# USRF02.net
KiCad netlist of a schematic drawn in Altium Designer
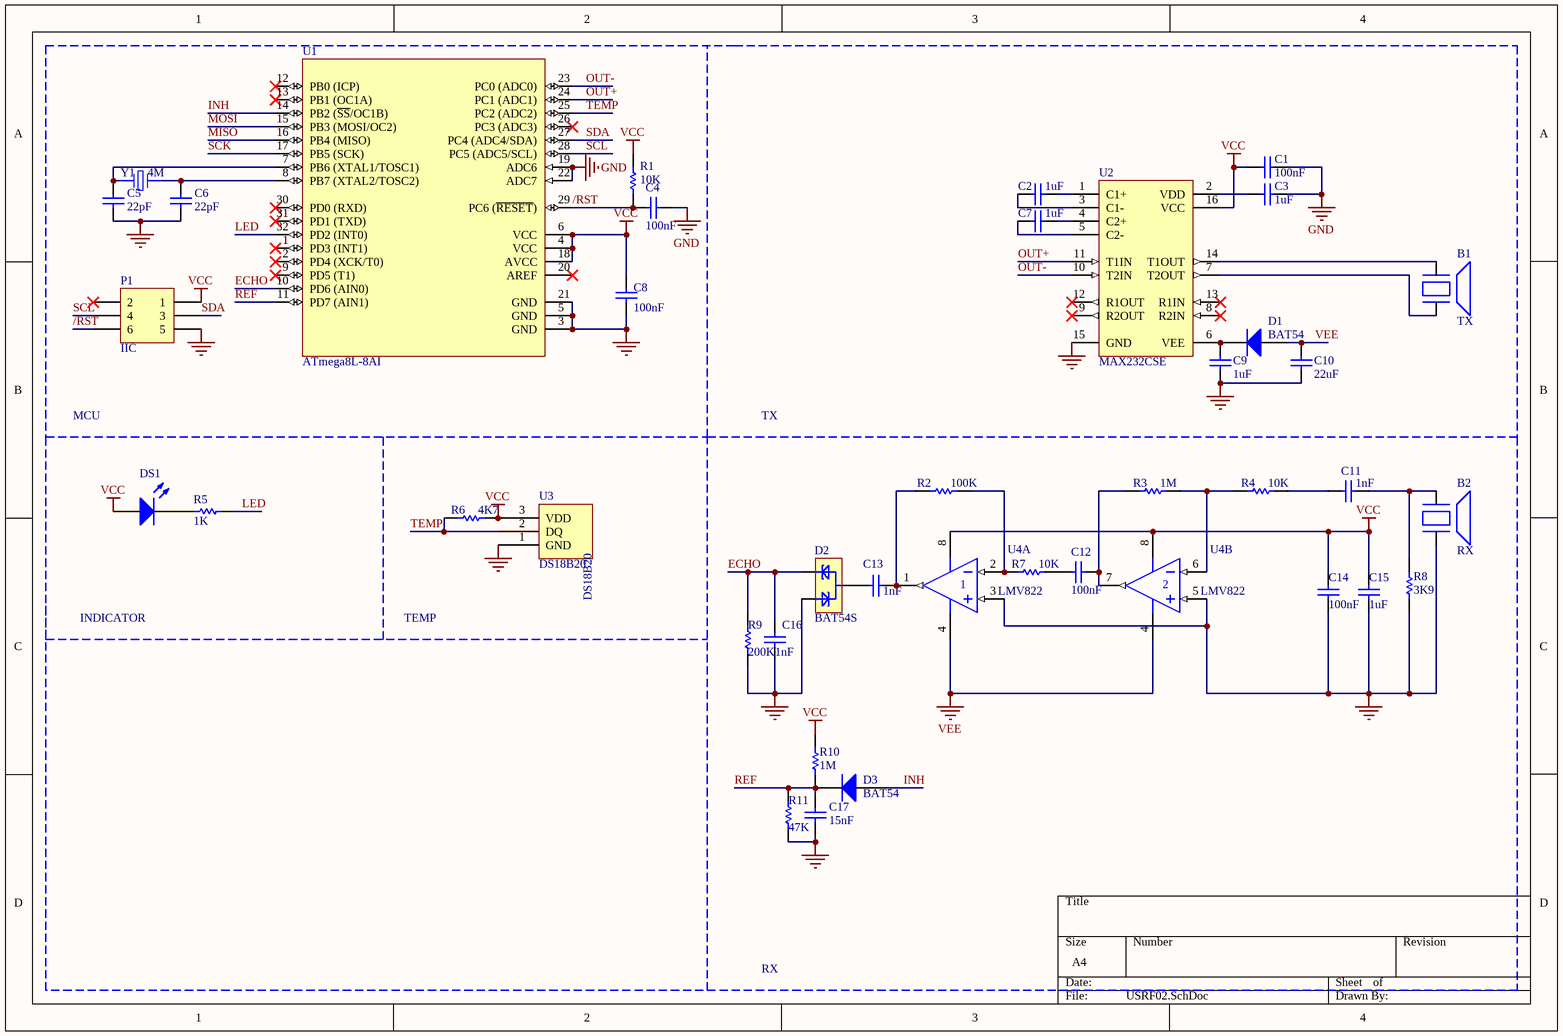
[diagram p0: USRF02.SchDoc]

(export (version "E")
  (design (tool "Eeschema 10.0.6"))
  (components
    (comp (ref "B1")
      (value "TX")
      (footprint "TCx40-12T/R/TR")
      (description "Ultrasonic TX/RX")
      (libsource (lib "Custom Lib") (part "Ultrasonic TX/RX"))
    )
    (comp (ref "B2")
      (value "RX")
      (footprint "TCx40-12T/R/TR")
      (description "Ultrasonic TX/RX")
      (libsource (lib "Custom Lib") (part "Ultrasonic TX/RX"))
    )
    (comp (ref "C1")
      (value "100nF")
      (footprint "CAPC2012N")
      (description "Capacitor")
      (fields (field (name "PUBLISHER") "Altium Limited"))
      (libsource (lib "Miscellaneous Devices") (part "Cap"))
    )
    (comp (ref "C2")
      (value "1uF")
      (footprint "CAPC2012N")
      (description "Capacitor")
      (fields (field (name "PUBLISHER") "Altium Limited"))
      (libsource (lib "Miscellaneous Devices") (part "Cap"))
    )
    (comp (ref "C3")
      (value "1uF")
      (footprint "CAPC2012N")
      (description "Capacitor")
      (fields (field (name "PUBLISHER") "Altium Limited"))
      (libsource (lib "Miscellaneous Devices") (part "Cap"))
    )
    (comp (ref "C4")
      (value "100nF")
      (footprint "CAPC2012N")
      (description "Capacitor")
      (fields (field (name "PUBLISHER") "Altium Limited"))
      (libsource (lib "Miscellaneous Devices") (part "Cap"))
    )
    (comp (ref "C5")
      (value "22pF")
      (footprint "CAPC2012N")
      (description "Capacitor")
      (fields (field (name "PUBLISHER") "Altium Limited"))
      (libsource (lib "Miscellaneous Devices") (part "Cap"))
    )
    (comp (ref "C6")
      (value "22pF")
      (footprint "CAPC2012N")
      (description "Capacitor")
      (fields (field (name "PUBLISHER") "Altium Limited"))
      (libsource (lib "Miscellaneous Devices") (part "Cap"))
    )
    (comp (ref "C7")
      (value "1uF")
      (footprint "CAPC2012N")
      (description "Capacitor")
      (fields (field (name "PUBLISHER") "Altium Limited"))
      (libsource (lib "Miscellaneous Devices") (part "Cap"))
    )
    (comp (ref "C8")
      (value "100nF")
      (footprint "CAPC2012N")
      (description "Capacitor")
      (fields (field (name "PUBLISHER") "Altium Limited"))
      (libsource (lib "Miscellaneous Devices") (part "Cap"))
    )
    (comp (ref "C9")
      (value "1uF")
      (footprint "CAPC2012N")
      (description "Capacitor")
      (fields (field (name "PUBLISHER") "Altium Limited"))
      (libsource (lib "Miscellaneous Devices") (part "Cap"))
    )
    (comp (ref "C10")
      (value "22uF")
      (footprint "CAPC2012N")
      (description "Capacitor")
      (fields (field (name "PUBLISHER") "Altium Limited"))
      (libsource (lib "Miscellaneous Devices") (part "Cap"))
    )
    (comp (ref "C11")
      (value "1nF")
      (footprint "CAPC2012N")
      (description "Capacitor")
      (fields (field (name "PUBLISHER") "Altium Limited"))
      (libsource (lib "Miscellaneous Devices") (part "Cap"))
    )
    (comp (ref "C12")
      (value "100nF")
      (footprint "CAPC2012N")
      (description "Capacitor")
      (fields (field (name "PUBLISHER") "Altium Limited"))
      (libsource (lib "Miscellaneous Devices") (part "Cap"))
    )
    (comp (ref "C13")
      (value "1nF")
      (footprint "CAPC2012N")
      (description "Capacitor")
      (fields (field (name "PUBLISHER") "Altium Limited"))
      (libsource (lib "Miscellaneous Devices") (part "Cap"))
    )
    (comp (ref "C14")
      (value "100nF")
      (footprint "CAPC2012N")
      (description "Capacitor")
      (fields (field (name "PUBLISHER") "Altium Limited"))
      (libsource (lib "Miscellaneous Devices") (part "Cap"))
    )
    (comp (ref "C15")
      (value "1uF")
      (footprint "CAPC2012N")
      (description "Capacitor")
      (fields (field (name "PUBLISHER") "Altium Limited"))
      (libsource (lib "Miscellaneous Devices") (part "Cap"))
    )
    (comp (ref "C16")
      (value "1nF")
      (footprint "CAPC2012N")
      (description "Capacitor")
      (fields (field (name "PUBLISHER") "Altium Limited"))
      (libsource (lib "Miscellaneous Devices") (part "Cap"))
    )
    (comp (ref "C17")
      (value "15nF")
      (footprint "CAPC2012N")
      (description "Capacitor")
      (fields (field (name "PUBLISHER") "Altium Limited"))
      (libsource (lib "Miscellaneous Devices") (part "Cap"))
    )
    (comp (ref "D1")
      (value "BAT54")
      (footprint "CD2012-0805")
      (description "High Conductance Fast Diode")
      (fields (field (name "PUBLISHER") "Altium Limited"))
      (libsource (lib "Miscellaneous Devices") (part "Diode 1N4148"))
    )
    (comp (ref "D2")
      (value "BAT54S")
      (footprint "SOT-23_L")
      (description "Schottky Diodes")
      (libsource (lib "Custom Lib") (part "BAT54S"))
    )
    (comp (ref "D3")
      (value "BAT54")
      (footprint "CD2012-0805")
      (description "High Conductance Fast Diode")
      (fields (field (name "PUBLISHER") "Altium Limited"))
      (libsource (lib "Miscellaneous Devices") (part "Diode 1N4148"))
    )
    (comp (ref "DS1")
      (value "LED3")
      (footprint "CD2012-0805")
      (description "Typical BLUE SiC LED")
      (fields (field (name "PUBLISHER") "Altium Limited"))
      (libsource (lib "Miscellaneous Devices") (part "LED3"))
    )
    (comp (ref "P1")
      (value "IIC")
      (footprint "HDR2X3")
      (description "Header, 3-Pin, Dual row")
      (fields (field (name "PUBLISHER") "Altium Limited"))
      (libsource (lib "Miscellaneous Connectors") (part "Header 3X2"))
    )
    (comp (ref "R1")
      (value "10K")
      (footprint "RESC2012N")
      (description "Resistor")
      (fields (field (name "PUBLISHER") "Altium Limited"))
      (libsource (lib "Miscellaneous Devices") (part "Res1"))
    )
    (comp (ref "R2")
      (value "100K")
      (footprint "RESC2012N")
      (description "Resistor")
      (fields (field (name "PUBLISHER") "Altium Limited"))
      (libsource (lib "Miscellaneous Devices") (part "Res1"))
    )
    (comp (ref "R3")
      (value "1M")
      (footprint "RESC2012N")
      (description "Resistor")
      (fields (field (name "PUBLISHER") "Altium Limited"))
      (libsource (lib "Miscellaneous Devices") (part "Res1"))
    )
    (comp (ref "R4")
      (value "10K")
      (footprint "RESC2012N")
      (description "Resistor")
      (fields (field (name "PUBLISHER") "Altium Limited"))
      (libsource (lib "Miscellaneous Devices") (part "Res1"))
    )
    (comp (ref "R5")
      (value "1K")
      (footprint "RESC2012N")
      (description "Resistor")
      (fields (field (name "PUBLISHER") "Altium Limited"))
      (libsource (lib "Miscellaneous Devices") (part "Res1"))
    )
    (comp (ref "R6")
      (value "4K7")
      (footprint "RESC2012N")
      (description "Resistor")
      (fields (field (name "PUBLISHER") "Altium Limited"))
      (libsource (lib "Miscellaneous Devices") (part "Res1"))
    )
    (comp (ref "R7")
      (value "10K")
      (footprint "RESC2012N")
      (description "Resistor")
      (fields (field (name "PUBLISHER") "Altium Limited"))
      (libsource (lib "Miscellaneous Devices") (part "Res1"))
    )
    (comp (ref "R8")
      (value "3K9")
      (footprint "RESC2012N")
      (description "Resistor")
      (fields (field (name "PUBLISHER") "Altium Limited"))
      (libsource (lib "Miscellaneous Devices") (part "Res1"))
    )
    (comp (ref "R9")
      (value "200K")
      (footprint "RESC2012N")
      (description "Resistor")
      (fields (field (name "PUBLISHER") "Altium Limited"))
      (libsource (lib "Miscellaneous Devices") (part "Res1"))
    )
    (comp (ref "R10")
      (value "1M")
      (footprint "RESC2012N")
      (description "Resistor")
      (fields (field (name "PUBLISHER") "Altium Limited"))
      (libsource (lib "Miscellaneous Devices") (part "Res1"))
    )
    (comp (ref "R11")
      (value "47K")
      (footprint "RESC2012N")
      (description "Resistor")
      (fields (field (name "PUBLISHER") "Altium Limited"))
      (libsource (lib "Miscellaneous Devices") (part "Res1"))
    )
    (comp (ref "U1")
      (value "ATmega8L-8AI")
      (footprint "32A_N")
      (description "8-Bit AVR Microcontroller with 8K Bytes of In-System Programmable Flash Memory")
      (fields (field (name "PUBLISHER") "Altium Limited"))
      (libsource (lib "Atmel Microcontroller 8-Bit AVR") (part "ATmega8L-8AI"))
    )
    (comp (ref "U2")
      (value "MAX232CSE")
      (footprint "NSO16_N")
      (description "+5V Powered, Multi-Channel RS-232 Driver/Receiver")
      (fields (field (name "PUBLISHER") "Altium Limited"))
      (libsource (lib "Maxim Communication Transceiver") (part "MAX232CSE"))
    )
    (comp (ref "U3")
      (value "DS18B20")
      (footprint "TO-92 (In Line)")
      (description "Programmable Resolution 1-Wire Digital Thermometer")
      (libsource (lib "Custom Lib") (part "DS18B20"))
    )
    (comp (ref "U4")
      (value "LMV822")
      (footprint "M08A_N")
      (description "Dual General-Purpose, Low-Voltage Rail-to-Rail Output Operational Amplifier")
      (fields (field (name "PUBLISHER") "Altium Limited"))
      (libsource (lib "NSC Operational Amplifier") (part "LMV358M"))
    )
    (comp (ref "Y1")
      (value "4M")
      (footprint "Crystal Oscillator 1")
      (description "2 Pins crystal")
      (libsource (lib "Custom Lib") (part "Crystal Oscillator 1"))
    )
  )
  (nets
    (net (code "1") (name "/ECHO") (class "Default")
      (node (ref "C16") (pin "1") (pinfunction "1_1") (pintype "passive"))
      (node (ref "D2") (pin "2") (pinfunction "2_2") (pintype "passive"))
      (node (ref "R9") (pin "2") (pinfunction "2_2") (pintype "passive"))
      (node (ref "U1") (pin "10") (pinfunction "PD6_(AIN0)_10") (pintype "bidirectional"))
    )
    (net (code "2") (name "/INH") (class "Default")
      (node (ref "D3") (pin "1") (pinfunction "A_1") (pintype "passive"))
      (node (ref "U1") (pin "14") (pinfunction "PB2_(~{SS}/OC1B)_14") (pintype "bidirectional"))
    )
    (net (code "3") (name "/LED") (class "Default")
      (node (ref "R5") (pin "2") (pinfunction "2_2") (pintype "passive"))
      (node (ref "U1") (pin "32") (pinfunction "PD2_(INT0)_32") (pintype "bidirectional"))
    )
    (net (code "4") (name "/MISO") (class "Default")
      (node (ref "U1") (pin "16") (pinfunction "PB4_(MISO)_16") (pintype "bidirectional"))
    )
    (net (code "5") (name "/MOSI") (class "Default")
      (node (ref "U1") (pin "15") (pinfunction "PB3_(MOSI/OC2)_15") (pintype "bidirectional"))
    )
    (net (code "6") (name "/OUT+") (class "Default")
      (node (ref "U1") (pin "24") (pinfunction "PC1_(ADC1)_24") (pintype "bidirectional"))
      (node (ref "U2") (pin "11") (pinfunction "T1IN_11") (pintype "input"))
    )
    (net (code "7") (name "/OUT-") (class "Default")
      (node (ref "U1") (pin "23") (pinfunction "PC0_(ADC0)_23") (pintype "bidirectional"))
      (node (ref "U2") (pin "10") (pinfunction "T2IN_10") (pintype "input"))
    )
    (net (code "8") (name "/REF") (class "Default")
      (node (ref "C17") (pin "1") (pinfunction "1_1") (pintype "passive"))
      (node (ref "D3") (pin "2") (pinfunction "K_2") (pintype "passive"))
      (node (ref "R10") (pin "2") (pinfunction "2_2") (pintype "passive"))
      (node (ref "R11") (pin "1") (pinfunction "1_1") (pintype "passive"))
      (node (ref "U1") (pin "11") (pinfunction "PD7_(AIN1)_11") (pintype "bidirectional"))
    )
    (net (code "9") (name "/SCK") (class "Default")
      (node (ref "U1") (pin "17") (pinfunction "PB5_(SCK)_17") (pintype "bidirectional"))
    )
    (net (code "10") (name "/SCL") (class "Default")
      (node (ref "P1") (pin "4") (pinfunction "4_4") (pintype "passive"))
      (node (ref "U1") (pin "28") (pinfunction "PC5_(ADC5/SCL)_28") (pintype "bidirectional"))
    )
    (net (code "11") (name "/SDA") (class "Default")
      (node (ref "P1") (pin "3") (pinfunction "3_3") (pintype "passive"))
      (node (ref "U1") (pin "27") (pinfunction "PC4_(ADC4/SDA)_27") (pintype "bidirectional"))
    )
    (net (code "12") (name "/TEMP") (class "Default")
      (node (ref "R6") (pin "1") (pinfunction "1_1") (pintype "passive"))
      (node (ref "U1") (pin "25") (pinfunction "PC2_(ADC2)_25") (pintype "bidirectional"))
      (node (ref "U3") (pin "2") (pinfunction "DQ_2") (pintype "passive"))
    )
    (net (code "13") (name "/{slash}RST") (class "Default")
      (node (ref "C4") (pin "1") (pinfunction "1_1") (pintype "passive"))
      (node (ref "P1") (pin "6") (pinfunction "6_6") (pintype "passive"))
      (node (ref "R1") (pin "1") (pinfunction "1_1") (pintype "passive"))
      (node (ref "U1") (pin "29") (pinfunction "PC6_(~{RESET})_29") (pintype "bidirectional"))
    )
    (net (code "14") (name "GND") (class "Default")
      (node (ref "B2") (pin "2") (pinfunction "2_2") (pintype "passive"))
      (node (ref "C1") (pin "2") (pinfunction "2_2") (pintype "passive"))
      (node (ref "C10") (pin "1") (pinfunction "1_1") (pintype "passive"))
      (node (ref "C14") (pin "2") (pinfunction "2_2") (pintype "passive"))
      (node (ref "C15") (pin "2") (pinfunction "2_2") (pintype "passive"))
      (node (ref "C16") (pin "2") (pinfunction "2_2") (pintype "passive"))
      (node (ref "C17") (pin "2") (pinfunction "2_2") (pintype "passive"))
      (node (ref "C3") (pin "2") (pinfunction "2_2") (pintype "passive"))
      (node (ref "C4") (pin "2") (pinfunction "2_2") (pintype "passive"))
      (node (ref "C5") (pin "1") (pinfunction "1_1") (pintype "passive"))
      (node (ref "C6") (pin "1") (pinfunction "1_1") (pintype "passive"))
      (node (ref "C8") (pin "2") (pinfunction "2_2") (pintype "passive"))
      (node (ref "C9") (pin "1") (pinfunction "1_1") (pintype "passive"))
      (node (ref "D2") (pin "1") (pinfunction "1_1") (pintype "passive"))
      (node (ref "P1") (pin "5") (pinfunction "5_5") (pintype "passive"))
      (node (ref "R11") (pin "2") (pinfunction "2_2") (pintype "passive"))
      (node (ref "R8") (pin "1") (pinfunction "1_1") (pintype "passive"))
      (node (ref "R9") (pin "1") (pinfunction "1_1") (pintype "passive"))
      (node (ref "U1") (pin "19") (pinfunction "ADC6_19") (pintype "input"))
      (node (ref "U1") (pin "21") (pinfunction "GND_21") (pintype "power_in"))
      (node (ref "U1") (pin "22") (pinfunction "ADC7_22") (pintype "input"))
      (node (ref "U1") (pin "3") (pinfunction "GND_3") (pintype "power_in"))
      (node (ref "U1") (pin "5") (pinfunction "GND_5") (pintype "power_in"))
      (node (ref "U2") (pin "15") (pinfunction "GND_15") (pintype "power_in"))
      (node (ref "U3") (pin "1") (pinfunction "GND_1") (pintype "passive"))
      (node (ref "U4") (pin "3") (pinfunction "IN+_3") (pintype "input"))
      (node (ref "U4") (pin "5") (pinfunction "IN+_5") (pintype "input"))
    )
    (net (code "15") (name "Net-(B2-Pad1)") (class "Default")
      (node (ref "B2") (pin "1") (pinfunction "1_1") (pintype "passive"))
      (node (ref "C11") (pin "2") (pinfunction "2_2") (pintype "passive"))
      (node (ref "R8") (pin "2") (pinfunction "2_2") (pintype "passive"))
    )
    (net (code "16") (name "Net-(C11-Pad1)") (class "Default")
      (node (ref "C11") (pin "1") (pinfunction "1_1") (pintype "passive"))
      (node (ref "R4") (pin "2") (pinfunction "2_2") (pintype "passive"))
    )
    (net (code "17") (name "Net-(C12-Pad2)") (class "Default")
      (node (ref "C12") (pin "2") (pinfunction "2_2") (pintype "passive"))
      (node (ref "R7") (pin "2") (pinfunction "2_2") (pintype "passive"))
    )
    (net (code "18") (name "Net-(C13-Pad2)") (class "Default")
      (node (ref "C13") (pin "2") (pinfunction "2_2") (pintype "passive"))
      (node (ref "D2") (pin "3") (pinfunction "3_3") (pintype "passive"))
    )
    (net (code "19") (name "Net-(D1-K)") (class "Default")
      (node (ref "C9") (pin "2") (pinfunction "2_2") (pintype "passive"))
      (node (ref "D1") (pin "2") (pinfunction "K_2") (pintype "passive"))
      (node (ref "U2") (pin "6") (pinfunction "VEE_6") (pintype "power_in"))
    )
    (net (code "20") (name "Net-(DS1-K)") (class "Default")
      (node (ref "DS1") (pin "2") (pinfunction "K_2") (pintype "passive"))
      (node (ref "R5") (pin "1") (pinfunction "1_1") (pintype "passive"))
    )
    (net (code "21") (name "Net-(U1-PB6_(XTAL1{slash}TOSC1))") (class "Default")
      (node (ref "C5") (pin "2") (pinfunction "2_2") (pintype "passive"))
      (node (ref "U1") (pin "7") (pinfunction "PB6_(XTAL1/TOSC1)_7") (pintype "bidirectional"))
      (node (ref "Y1") (pin "1") (pinfunction "1_1") (pintype "passive"))
    )
    (net (code "22") (name "Net-(U1-PB7_(XTAL2{slash}TOSC2))") (class "Default")
      (node (ref "C6") (pin "2") (pinfunction "2_2") (pintype "passive"))
      (node (ref "U1") (pin "8") (pinfunction "PB7_(XTAL2/TOSC2)_8") (pintype "bidirectional"))
      (node (ref "Y1") (pin "2") (pinfunction "2_2") (pintype "passive"))
    )
    (net (code "23") (name "Net-(U2-C1+)") (class "Default")
      (node (ref "C2") (pin "1") (pinfunction "1_1") (pintype "passive"))
      (node (ref "U2") (pin "1") (pinfunction "C1+_1") (pintype "passive"))
    )
    (net (code "24") (name "Net-(U2-C1-)") (class "Default")
      (node (ref "C2") (pin "2") (pinfunction "2_2") (pintype "passive"))
      (node (ref "U2") (pin "3") (pinfunction "C1-_3") (pintype "passive"))
    )
    (net (code "25") (name "Net-(U2-C2+)") (class "Default")
      (node (ref "C7") (pin "1") (pinfunction "1_1") (pintype "passive"))
      (node (ref "U2") (pin "4") (pinfunction "C2+_4") (pintype "passive"))
    )
    (net (code "26") (name "Net-(U2-C2-)") (class "Default")
      (node (ref "C7") (pin "2") (pinfunction "2_2") (pintype "passive"))
      (node (ref "U2") (pin "5") (pinfunction "C2-_5") (pintype "passive"))
    )
    (net (code "27") (name "Net-(U2-T1OUT)") (class "Default")
      (node (ref "B1") (pin "1") (pinfunction "1_1") (pintype "passive"))
      (node (ref "U2") (pin "14") (pinfunction "T1OUT_14") (pintype "output"))
    )
    (net (code "28") (name "Net-(U2-T2OUT)") (class "Default")
      (node (ref "B1") (pin "2") (pinfunction "2_2") (pintype "passive"))
      (node (ref "U2") (pin "7") (pinfunction "T2OUT_7") (pintype "output"))
    )
    (net (code "29") (name "Net-(U2-VDD)") (class "Default")
      (node (ref "C3") (pin "1") (pinfunction "1_1") (pintype "passive"))
      (node (ref "U2") (pin "2") (pinfunction "VDD_2") (pintype "power_in"))
    )
    (net (code "30") (name "Net-(U4A-IN-)") (class "Default")
      (node (ref "R2") (pin "2") (pinfunction "2_2") (pintype "passive"))
      (node (ref "R7") (pin "1") (pinfunction "1_1") (pintype "passive"))
      (node (ref "U4") (pin "2") (pinfunction "IN-_2") (pintype "input"))
    )
    (net (code "31") (name "Net-(U4A-OUT)") (class "Default")
      (node (ref "C13") (pin "1") (pinfunction "1_1") (pintype "passive"))
      (node (ref "R2") (pin "1") (pinfunction "1_1") (pintype "passive"))
      (node (ref "U4") (pin "1") (pinfunction "OUT_1") (pintype "output"))
    )
    (net (code "32") (name "Net-(U4B-IN-)") (class "Default")
      (node (ref "R3") (pin "2") (pinfunction "2_2") (pintype "passive"))
      (node (ref "R4") (pin "1") (pinfunction "1_1") (pintype "passive"))
      (node (ref "U4") (pin "6") (pinfunction "IN-_6") (pintype "input"))
    )
    (net (code "33") (name "Net-(U4B-OUT)") (class "Default")
      (node (ref "C12") (pin "1") (pinfunction "1_1") (pintype "passive"))
      (node (ref "R3") (pin "1") (pinfunction "1_1") (pintype "passive"))
      (node (ref "U4") (pin "7") (pinfunction "OUT_7") (pintype "output"))
    )
    (net (code "34") (name "VCC") (class "Default")
      (node (ref "C1") (pin "1") (pinfunction "1_1") (pintype "passive"))
      (node (ref "C14") (pin "1") (pinfunction "1_1") (pintype "passive"))
      (node (ref "C15") (pin "1") (pinfunction "1_1") (pintype "passive"))
      (node (ref "C8") (pin "1") (pinfunction "1_1") (pintype "passive"))
      (node (ref "DS1") (pin "1") (pinfunction "A_1") (pintype "passive"))
      (node (ref "P1") (pin "1") (pinfunction "1_1") (pintype "passive"))
      (node (ref "R1") (pin "2") (pinfunction "2_2") (pintype "passive"))
      (node (ref "R10") (pin "1") (pinfunction "1_1") (pintype "passive"))
      (node (ref "R6") (pin "2") (pinfunction "2_2") (pintype "passive"))
      (node (ref "U1") (pin "18") (pinfunction "AVCC_18") (pintype "power_in"))
      (node (ref "U1") (pin "4") (pinfunction "VCC_4") (pintype "power_in"))
      (node (ref "U1") (pin "6") (pinfunction "VCC_6") (pintype "power_in"))
      (node (ref "U2") (pin "16") (pinfunction "VCC_16") (pintype "power_in"))
      (node (ref "U3") (pin "3") (pinfunction "VDD_3") (pintype "passive"))
      (node (ref "U4") (pin "8") (pinfunction "V+_8") (pintype "power_in"))
    )
    (net (code "35") (name "VEE") (class "Default")
      (node (ref "C10") (pin "2") (pinfunction "2_2") (pintype "passive"))
      (node (ref "D1") (pin "1") (pinfunction "A_1") (pintype "passive"))
      (node (ref "U4") (pin "4") (pinfunction "V-_4") (pintype "power_in"))
    )
    (net (code "36") (name "unconnected-(P1-Pad2)") (class "Default")
      (node (ref "P1") (pin "2") (pinfunction "2_2") (pintype "passive+no_connect"))
    )
    (net (code "37") (name "unconnected-(U1-AREF-Pad20)") (class "Default")
      (node (ref "U1") (pin "20") (pinfunction "AREF_20") (pintype "passive+no_connect"))
    )
    (net (code "38") (name "unconnected-(U1-PB0_(ICP)-Pad12)") (class "Default")
      (node (ref "U1") (pin "12") (pinfunction "PB0_(ICP)_12") (pintype "bidirectional+no_connect"))
    )
    (net (code "39") (name "unconnected-(U1-PB1_(OC1A)-Pad13)") (class "Default")
      (node (ref "U1") (pin "13") (pinfunction "PB1_(OC1A)_13") (pintype "bidirectional+no_connect"))
    )
    (net (code "40") (name "unconnected-(U1-PC3_(ADC3)-Pad26)") (class "Default")
      (node (ref "U1") (pin "26") (pinfunction "PC3_(ADC3)_26") (pintype "bidirectional+no_connect"))
    )
    (net (code "41") (name "unconnected-(U1-PD0_(RXD)-Pad30)") (class "Default")
      (node (ref "U1") (pin "30") (pinfunction "PD0_(RXD)_30") (pintype "bidirectional+no_connect"))
    )
    (net (code "42") (name "unconnected-(U1-PD1_(TXD)-Pad31)") (class "Default")
      (node (ref "U1") (pin "31") (pinfunction "PD1_(TXD)_31") (pintype "bidirectional+no_connect"))
    )
    (net (code "43") (name "unconnected-(U1-PD3_(INT1)-Pad1)") (class "Default")
      (node (ref "U1") (pin "1") (pinfunction "PD3_(INT1)_1") (pintype "bidirectional+no_connect"))
    )
    (net (code "44") (name "unconnected-(U1-PD4_(XCK{slash}T0)-Pad2)") (class "Default")
      (node (ref "U1") (pin "2") (pinfunction "PD4_(XCK/T0)_2") (pintype "bidirectional+no_connect"))
    )
    (net (code "45") (name "unconnected-(U1-PD5_(T1)-Pad9)") (class "Default")
      (node (ref "U1") (pin "9") (pinfunction "PD5_(T1)_9") (pintype "bidirectional+no_connect"))
    )
    (net (code "46") (name "unconnected-(U2-R1IN-Pad13)") (class "Default")
      (node (ref "U2") (pin "13") (pinfunction "R1IN_13") (pintype "input+no_connect"))
    )
    (net (code "47") (name "unconnected-(U2-R1OUT-Pad12)") (class "Default")
      (node (ref "U2") (pin "12") (pinfunction "R1OUT_12") (pintype "output+no_connect"))
    )
    (net (code "48") (name "unconnected-(U2-R2IN-Pad8)") (class "Default")
      (node (ref "U2") (pin "8") (pinfunction "R2IN_8") (pintype "input+no_connect"))
    )
    (net (code "49") (name "unconnected-(U2-R2OUT-Pad9)") (class "Default")
      (node (ref "U2") (pin "9") (pinfunction "R2OUT_9") (pintype "output+no_connect"))
    )
  )
)
